# M8-Quad-420mA-Boost.net
KiCad netlist of a schematic drawn in EAGLE
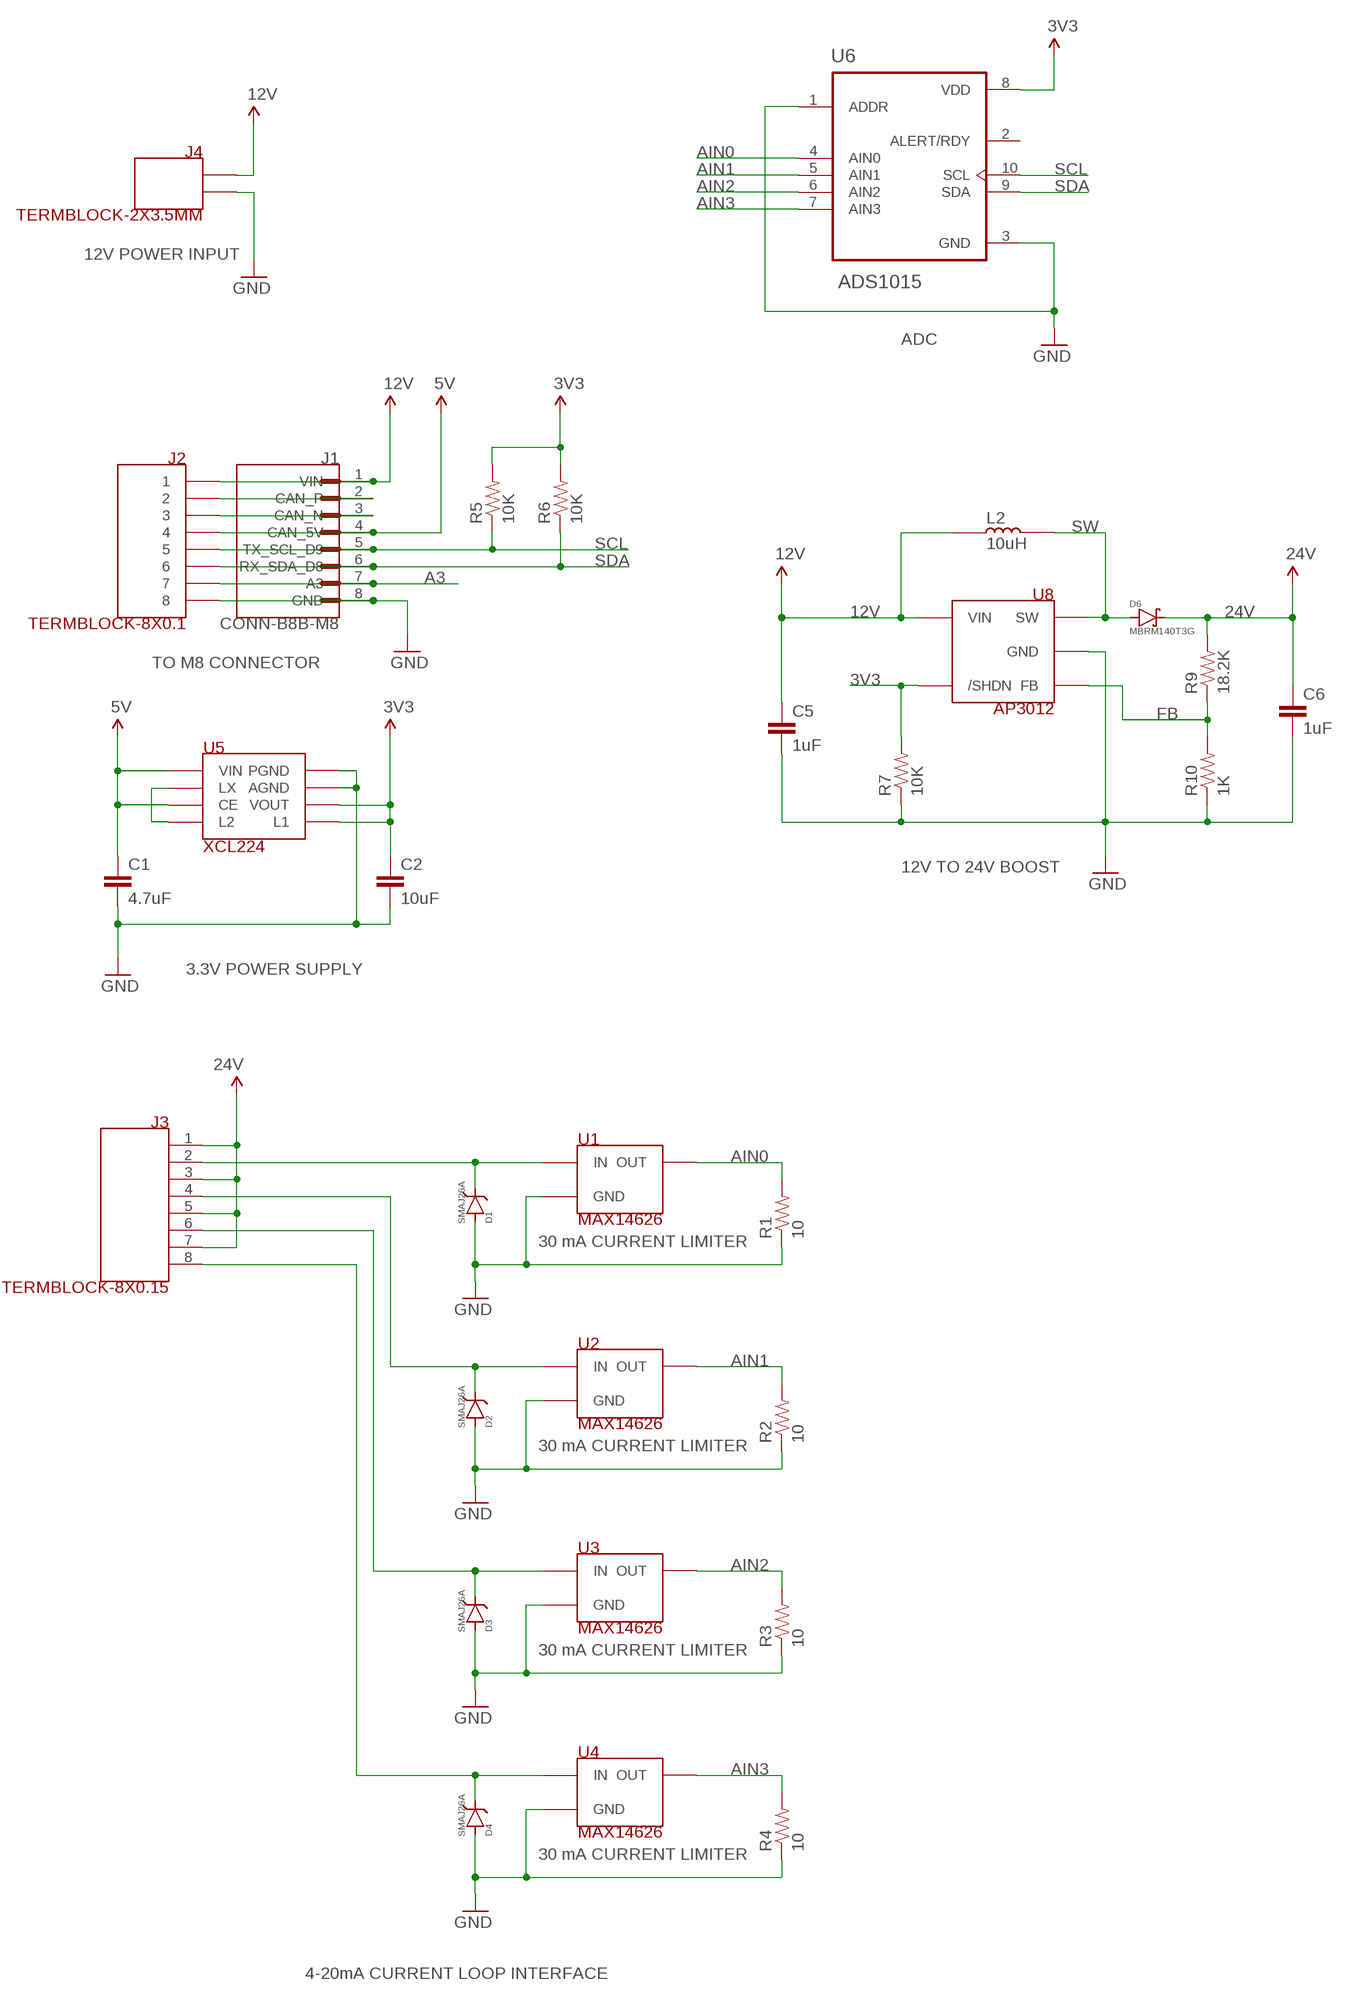
[diagram p0: schematic, sheet 1]

(export (version "E")
  (design (tool "Eeschema 10.0.6"))
  (components
    (comp (ref "C1")
      (value "4.7uF")
      (footprint "eagle-import:0603-CAP")
      (libsource (lib "eagle-import") (part "CAP-4.7UF-0603"))
    )
    (comp (ref "C2")
      (value "10uF")
      (footprint "eagle-import:0603-CAP")
      (libsource (lib "eagle-import") (part "CAP-10UF-0603"))
    )
    (comp (ref "C5")
      (value "1uF")
      (footprint "eagle-import:0603-CAP")
      (libsource (lib "eagle-import") (part "CAP-1UF-0603.DEV"))
    )
    (comp (ref "C6")
      (value "1uF")
      (footprint "eagle-import:0603-CAP")
      (libsource (lib "eagle-import") (part "CAP-1UF-0603.DEV"))
    )
    (comp (ref "D1")
      (value "SMAJ26A")
      (footprint "eagle-import:DO-214AC-LITTELFUSE")
      (libsource (lib "eagle-import") (part "DIODE-TVS-SMAJ26A"))
    )
    (comp (ref "D2")
      (value "SMAJ26A")
      (footprint "eagle-import:DO-214AC-LITTELFUSE")
      (libsource (lib "eagle-import") (part "DIODE-TVS-SMAJ26A"))
    )
    (comp (ref "D3")
      (value "SMAJ26A")
      (footprint "eagle-import:DO-214AC-LITTELFUSE")
      (libsource (lib "eagle-import") (part "DIODE-TVS-SMAJ26A"))
    )
    (comp (ref "D4")
      (value "SMAJ26A")
      (footprint "eagle-import:DO-214AC-LITTELFUSE")
      (libsource (lib "eagle-import") (part "DIODE-TVS-SMAJ26A"))
    )
    (comp (ref "D6")
      (value "MBRM140T3G")
      (footprint "eagle-import:MBRM140T3G")
      (libsource (lib "eagle-import") (part "MBRM140T3G"))
    )
    (comp (ref "J1")
      (value "CONN-B8B-M8")
      (footprint "eagle-import:JST_B8B-PH-SM4-TB(LF)(SN)")
      (libsource (lib "eagle-import") (part "CONN-B8B-M8"))
    )
    (comp (ref "J2")
      (value "TERMBLOCK-8X0.1")
      (footprint "eagle-import:TERMBLOCK-8X0.1")
      (libsource (lib "eagle-import") (part "TERMBLOCK-8X0.1"))
    )
    (comp (ref "J3")
      (value "TERMBLOCK-8X0.15")
      (footprint "eagle-import:TERMBLOCK-8X0.15")
      (libsource (lib "eagle-import") (part "TERMBLOCK-8X0.15"))
    )
    (comp (ref "J4")
      (value "TERMBLOCK-2X3.5MM")
      (footprint "eagle-import:TERMBLOCK-2X3.5MM")
      (libsource (lib "eagle-import") (part "TERMBLOCK-2X3.5MM"))
    )
    (comp (ref "L2")
      (value "10uH")
      (footprint "eagle-import:BOURNS-INDUCTOR-3X3")
      (libsource (lib "eagle-import") (part "INDUCTOR-10UH"))
    )
    (comp (ref "R1")
      (value "10")
      (footprint "eagle-import:0603-RES")
      (libsource (lib "eagle-import") (part "RES-100-0603.DEV"))
    )
    (comp (ref "R2")
      (value "10")
      (footprint "eagle-import:0603-RES")
      (libsource (lib "eagle-import") (part "RES-100-0603.DEV"))
    )
    (comp (ref "R3")
      (value "10")
      (footprint "eagle-import:0603-RES")
      (libsource (lib "eagle-import") (part "RES-100-0603.DEV"))
    )
    (comp (ref "R4")
      (value "10")
      (footprint "eagle-import:0603-RES")
      (libsource (lib "eagle-import") (part "RES-100-0603.DEV"))
    )
    (comp (ref "R5")
      (value "10K")
      (footprint "eagle-import:0603-RES")
      (libsource (lib "eagle-import") (part "RES-10K-06030603"))
    )
    (comp (ref "R6")
      (value "10K")
      (footprint "eagle-import:0603-RES")
      (libsource (lib "eagle-import") (part "RES-10K-06030603"))
    )
    (comp (ref "R7")
      (value "10K")
      (footprint "eagle-import:0603-RES")
      (libsource (lib "eagle-import") (part "RES-10K-06030603"))
    )
    (comp (ref "R9")
      (value "18.2K")
      (footprint "eagle-import:0603-RES")
      (libsource (lib "eagle-import") (part "RES-18.2K-06030603"))
    )
    (comp (ref "R10")
      (value "1K")
      (footprint "eagle-import:0603-RES")
      (libsource (lib "eagle-import") (part "RES-2.2K-06030603"))
    )
    (comp (ref "U1")
      (value "MAX14626")
      (footprint "eagle-import:6-TDFN-MAXIM")
      (libsource (lib "eagle-import") (part "MAX14626"))
    )
    (comp (ref "U2")
      (value "MAX14626")
      (footprint "eagle-import:6-TDFN-MAXIM")
      (libsource (lib "eagle-import") (part "MAX14626"))
    )
    (comp (ref "U3")
      (value "MAX14626")
      (footprint "eagle-import:6-TDFN-MAXIM")
      (libsource (lib "eagle-import") (part "MAX14626"))
    )
    (comp (ref "U4")
      (value "MAX14626")
      (footprint "eagle-import:6-TDFN-MAXIM")
      (libsource (lib "eagle-import") (part "MAX14626"))
    )
    (comp (ref "U5")
      (value "XCL224")
      (footprint "eagle-import:REG-XCL223-LESS-CREAM")
      (libsource (lib "eagle-import") (part "REG-XCL223"))
    )
    (comp (ref "U6")
      (value "ADS1015")
      (footprint "eagle-import:SOP50P490X110-10N")
      (fields
        (field (name "DIGI-KEY_PART_NUMBER") "296-41185-1-ND")
        (field (name "MF") "Texas Instruments")
        (field (name "MP") "ADS1015IDGSR")
      )
      (libsource (lib "eagle-import") (part "ADS1015IDGSR"))
    )
    (comp (ref "U8")
      (value "AP3012")
      (footprint "eagle-import:SOT-23-5")
      (libsource (lib "eagle-import") (part "AP3012"))
    )
  )
  (nets
    (net (code "1") (name "/A3") (class "Default")
      (node (ref "J1") (pin "7") (pinfunction "A3_7") (pintype "passive"))
      (node (ref "J2") (pin "P$7") (pinfunction "7_P$7") (pintype "passive"))
    )
    (net (code "2") (name "/AIN0") (class "Default")
      (node (ref "R1") (pin "2") (pinfunction "2_2") (pintype "passive"))
      (node (ref "U1") (pin "6") (pinfunction "OUT_6") (pintype "bidirectional"))
      (node (ref "U6") (pin "4") (pinfunction "AIN0_4") (pintype "input"))
    )
    (net (code "3") (name "/AIN1") (class "Default")
      (node (ref "R2") (pin "2") (pinfunction "2_2") (pintype "passive"))
      (node (ref "U2") (pin "6") (pinfunction "OUT_6") (pintype "bidirectional"))
      (node (ref "U6") (pin "5") (pinfunction "AIN1_5") (pintype "input"))
    )
    (net (code "4") (name "/AIN2") (class "Default")
      (node (ref "R3") (pin "2") (pinfunction "2_2") (pintype "passive"))
      (node (ref "U3") (pin "6") (pinfunction "OUT_6") (pintype "bidirectional"))
      (node (ref "U6") (pin "6") (pinfunction "AIN2_6") (pintype "input"))
    )
    (net (code "5") (name "/AIN3") (class "Default")
      (node (ref "R4") (pin "2") (pinfunction "2_2") (pintype "passive"))
      (node (ref "U4") (pin "6") (pinfunction "OUT_6") (pintype "bidirectional"))
      (node (ref "U6") (pin "7") (pinfunction "AIN3_7") (pintype "input"))
    )
    (net (code "6") (name "/FB") (class "Default")
      (node (ref "R10") (pin "2") (pinfunction "2_2") (pintype "passive"))
      (node (ref "R9") (pin "1") (pinfunction "1_1") (pintype "passive"))
      (node (ref "U8") (pin "3") (pinfunction "FB_3") (pintype "input"))
    )
    (net (code "7") (name "/SCL") (class "Default")
      (node (ref "J1") (pin "5") (pinfunction "TX_SCL_D9_5") (pintype "passive"))
      (node (ref "J2") (pin "P$5") (pinfunction "5_P$5") (pintype "passive"))
      (node (ref "R5") (pin "1") (pinfunction "1_1") (pintype "passive"))
      (node (ref "U6") (pin "10") (pinfunction "SCL_10") (pintype "input"))
    )
    (net (code "8") (name "/SDA") (class "Default")
      (node (ref "J1") (pin "6") (pinfunction "RX_SDA_D8_6") (pintype "passive"))
      (node (ref "J2") (pin "P$6") (pinfunction "6_P$6") (pintype "passive"))
      (node (ref "R6") (pin "1") (pinfunction "1_1") (pintype "passive"))
      (node (ref "U6") (pin "9") (pinfunction "SDA_9") (pintype "bidirectional"))
    )
    (net (code "9") (name "/SW") (class "Default")
      (node (ref "D6") (pin "2") (pinfunction "ANODE_2") (pintype "bidirectional"))
      (node (ref "L2") (pin "2") (pinfunction "P$2_2") (pintype "passive"))
      (node (ref "U8") (pin "1") (pinfunction "SW_1") (pintype "output"))
    )
    (net (code "10") (name "3V3") (class "Default")
      (node (ref "C2") (pin "1") (pinfunction "1_1") (pintype "passive"))
      (node (ref "R5") (pin "2") (pinfunction "2_2") (pintype "passive"))
      (node (ref "R6") (pin "2") (pinfunction "2_2") (pintype "passive"))
      (node (ref "R7") (pin "2") (pinfunction "2_2") (pintype "passive"))
      (node (ref "U5") (pin "3") (pinfunction "VOUT_3") (pintype "passive"))
      (node (ref "U5") (pin "7") (pinfunction "L1_7") (pintype "passive"))
      (node (ref "U6") (pin "8") (pinfunction "VDD_8") (pintype "power_in"))
      (node (ref "U8") (pin "4") (pinfunction "/SHDN_4") (pintype "input"))
    )
    (net (code "11") (name "5V") (class "Default")
      (node (ref "C1") (pin "1") (pinfunction "1_1") (pintype "passive"))
      (node (ref "J1") (pin "4") (pinfunction "CAN_5V_4") (pintype "passive"))
      (node (ref "J2") (pin "P$4") (pinfunction "4_P$4") (pintype "passive"))
      (node (ref "U5") (pin "4") (pinfunction "CE_4") (pintype "input"))
      (node (ref "U5") (pin "6") (pinfunction "VIN_6") (pintype "power_in"))
    )
    (net (code "12") (name "12V") (class "Default")
      (node (ref "C5") (pin "1") (pinfunction "1_1") (pintype "passive"))
      (node (ref "J1") (pin "1") (pinfunction "VIN_1") (pintype "passive"))
      (node (ref "J2") (pin "P$1") (pinfunction "1_P$1") (pintype "passive"))
      (node (ref "J4") (pin "1") (pinfunction "1_1") (pintype "passive"))
      (node (ref "L2") (pin "1") (pinfunction "P$1_1") (pintype "passive"))
      (node (ref "U8") (pin "5") (pinfunction "VIN_5") (pintype "power_in"))
    )
    (net (code "13") (name "24V") (class "Default")
      (node (ref "C6") (pin "1") (pinfunction "1_1") (pintype "passive"))
      (node (ref "D6") (pin "1") (pinfunction "CATHODE_1") (pintype "bidirectional"))
      (node (ref "J3") (pin "1") (pinfunction "1_1") (pintype "passive"))
      (node (ref "J3") (pin "3") (pinfunction "3_3") (pintype "passive"))
      (node (ref "J3") (pin "5") (pinfunction "5_5") (pintype "passive"))
      (node (ref "J3") (pin "7") (pinfunction "7_7") (pintype "passive"))
      (node (ref "R9") (pin "2") (pinfunction "2_2") (pintype "passive"))
    )
    (net (code "14") (name "GND") (class "Default")
      (node (ref "C1") (pin "2") (pinfunction "2_2") (pintype "passive"))
      (node (ref "C2") (pin "2") (pinfunction "2_2") (pintype "passive"))
      (node (ref "C5") (pin "2") (pinfunction "2_2") (pintype "passive"))
      (node (ref "C6") (pin "2") (pinfunction "2_2") (pintype "passive"))
      (node (ref "D1") (pin "A") (pinfunction "ANODE_A") (pintype "bidirectional"))
      (node (ref "D2") (pin "A") (pinfunction "ANODE_A") (pintype "bidirectional"))
      (node (ref "D3") (pin "A") (pinfunction "ANODE_A") (pintype "bidirectional"))
      (node (ref "D4") (pin "A") (pinfunction "ANODE_A") (pintype "bidirectional"))
      (node (ref "J1") (pin "8") (pinfunction "GND_8") (pintype "passive"))
      (node (ref "J2") (pin "P$8") (pinfunction "8_P$8") (pintype "passive"))
      (node (ref "J4") (pin "2") (pinfunction "2_2") (pintype "passive"))
      (node (ref "R1") (pin "1") (pinfunction "1_1") (pintype "passive"))
      (node (ref "R10") (pin "1") (pinfunction "1_1") (pintype "passive"))
      (node (ref "R2") (pin "1") (pinfunction "1_1") (pintype "passive"))
      (node (ref "R3") (pin "1") (pinfunction "1_1") (pintype "passive"))
      (node (ref "R4") (pin "1") (pinfunction "1_1") (pintype "passive"))
      (node (ref "R7") (pin "1") (pinfunction "1_1") (pintype "passive"))
      (node (ref "U1") (pin "2") (pinfunction "GND_2") (pintype "passive"))
      (node (ref "U1") (pin "3") (pinfunction "GND_3") (pintype "passive"))
      (node (ref "U1") (pin "4") (pinfunction "GND_4") (pintype "passive"))
      (node (ref "U1") (pin "5") (pinfunction "GND_5") (pintype "passive"))
      (node (ref "U1") (pin "EP") (pinfunction "GND_EP") (pintype "passive"))
      (node (ref "U2") (pin "2") (pinfunction "GND_2") (pintype "passive"))
      (node (ref "U2") (pin "3") (pinfunction "GND_3") (pintype "passive"))
      (node (ref "U2") (pin "4") (pinfunction "GND_4") (pintype "passive"))
      (node (ref "U2") (pin "5") (pinfunction "GND_5") (pintype "passive"))
      (node (ref "U2") (pin "EP") (pinfunction "GND_EP") (pintype "passive"))
      (node (ref "U3") (pin "2") (pinfunction "GND_2") (pintype "passive"))
      (node (ref "U3") (pin "3") (pinfunction "GND_3") (pintype "passive"))
      (node (ref "U3") (pin "4") (pinfunction "GND_4") (pintype "passive"))
      (node (ref "U3") (pin "5") (pinfunction "GND_5") (pintype "passive"))
      (node (ref "U3") (pin "EP") (pinfunction "GND_EP") (pintype "passive"))
      (node (ref "U4") (pin "2") (pinfunction "GND_2") (pintype "passive"))
      (node (ref "U4") (pin "3") (pinfunction "GND_3") (pintype "passive"))
      (node (ref "U4") (pin "4") (pinfunction "GND_4") (pintype "passive"))
      (node (ref "U4") (pin "5") (pinfunction "GND_5") (pintype "passive"))
      (node (ref "U4") (pin "EP") (pinfunction "GND_EP") (pintype "passive"))
      (node (ref "U5") (pin "1") (pinfunction "PGND_1") (pintype "passive"))
      (node (ref "U5") (pin "2") (pinfunction "AGND_2") (pintype "passive"))
      (node (ref "U6") (pin "1") (pinfunction "ADDR_1") (pintype "input"))
      (node (ref "U6") (pin "3") (pinfunction "GND_3") (pintype "power_in"))
      (node (ref "U8") (pin "2") (pinfunction "GND_2") (pintype "passive"))
    )
    (net (code "15") (name "Net-(D1-CATHODE)") (class "Default")
      (node (ref "D1") (pin "C") (pinfunction "CATHODE_C") (pintype "bidirectional"))
      (node (ref "J3") (pin "2") (pinfunction "2_2") (pintype "passive"))
      (node (ref "U1") (pin "1") (pinfunction "IN_1") (pintype "passive"))
    )
    (net (code "16") (name "Net-(D2-CATHODE)") (class "Default")
      (node (ref "D2") (pin "C") (pinfunction "CATHODE_C") (pintype "bidirectional"))
      (node (ref "J3") (pin "4") (pinfunction "4_4") (pintype "passive"))
      (node (ref "U2") (pin "1") (pinfunction "IN_1") (pintype "passive"))
    )
    (net (code "17") (name "Net-(D3-CATHODE)") (class "Default")
      (node (ref "D3") (pin "C") (pinfunction "CATHODE_C") (pintype "bidirectional"))
      (node (ref "J3") (pin "6") (pinfunction "6_6") (pintype "passive"))
      (node (ref "U3") (pin "1") (pinfunction "IN_1") (pintype "passive"))
    )
    (net (code "18") (name "Net-(D4-CATHODE)") (class "Default")
      (node (ref "D4") (pin "C") (pinfunction "CATHODE_C") (pintype "bidirectional"))
      (node (ref "J3") (pin "8") (pinfunction "8_8") (pintype "passive"))
      (node (ref "U4") (pin "1") (pinfunction "IN_1") (pintype "passive"))
    )
    (net (code "19") (name "Net-(J1-CAN_N)") (class "Default")
      (node (ref "J1") (pin "3") (pinfunction "CAN_N_3") (pintype "passive"))
      (node (ref "J2") (pin "P$3") (pinfunction "3_P$3") (pintype "passive"))
    )
    (net (code "20") (name "Net-(J1-CAN_P)") (class "Default")
      (node (ref "J1") (pin "2") (pinfunction "CAN_P_2") (pintype "passive"))
      (node (ref "J2") (pin "P$2") (pinfunction "2_P$2") (pintype "passive"))
    )
    (net (code "21") (name "Net-(U5-L2)") (class "Default")
      (node (ref "U5") (pin "5") (pinfunction "LX_5") (pintype "passive"))
      (node (ref "U5") (pin "8") (pinfunction "L2_8") (pintype "passive"))
    )
    (net (code "22") (name "unconnected-(U6-ALERT{slash}RDY-Pad2)") (class "Default")
      (node (ref "U6") (pin "2") (pinfunction "ALERT/RDY_2") (pintype "output"))
    )
  )
)
